# DSO_Trig.net
KiCad netlist of a schematic drawn in Altium Designer
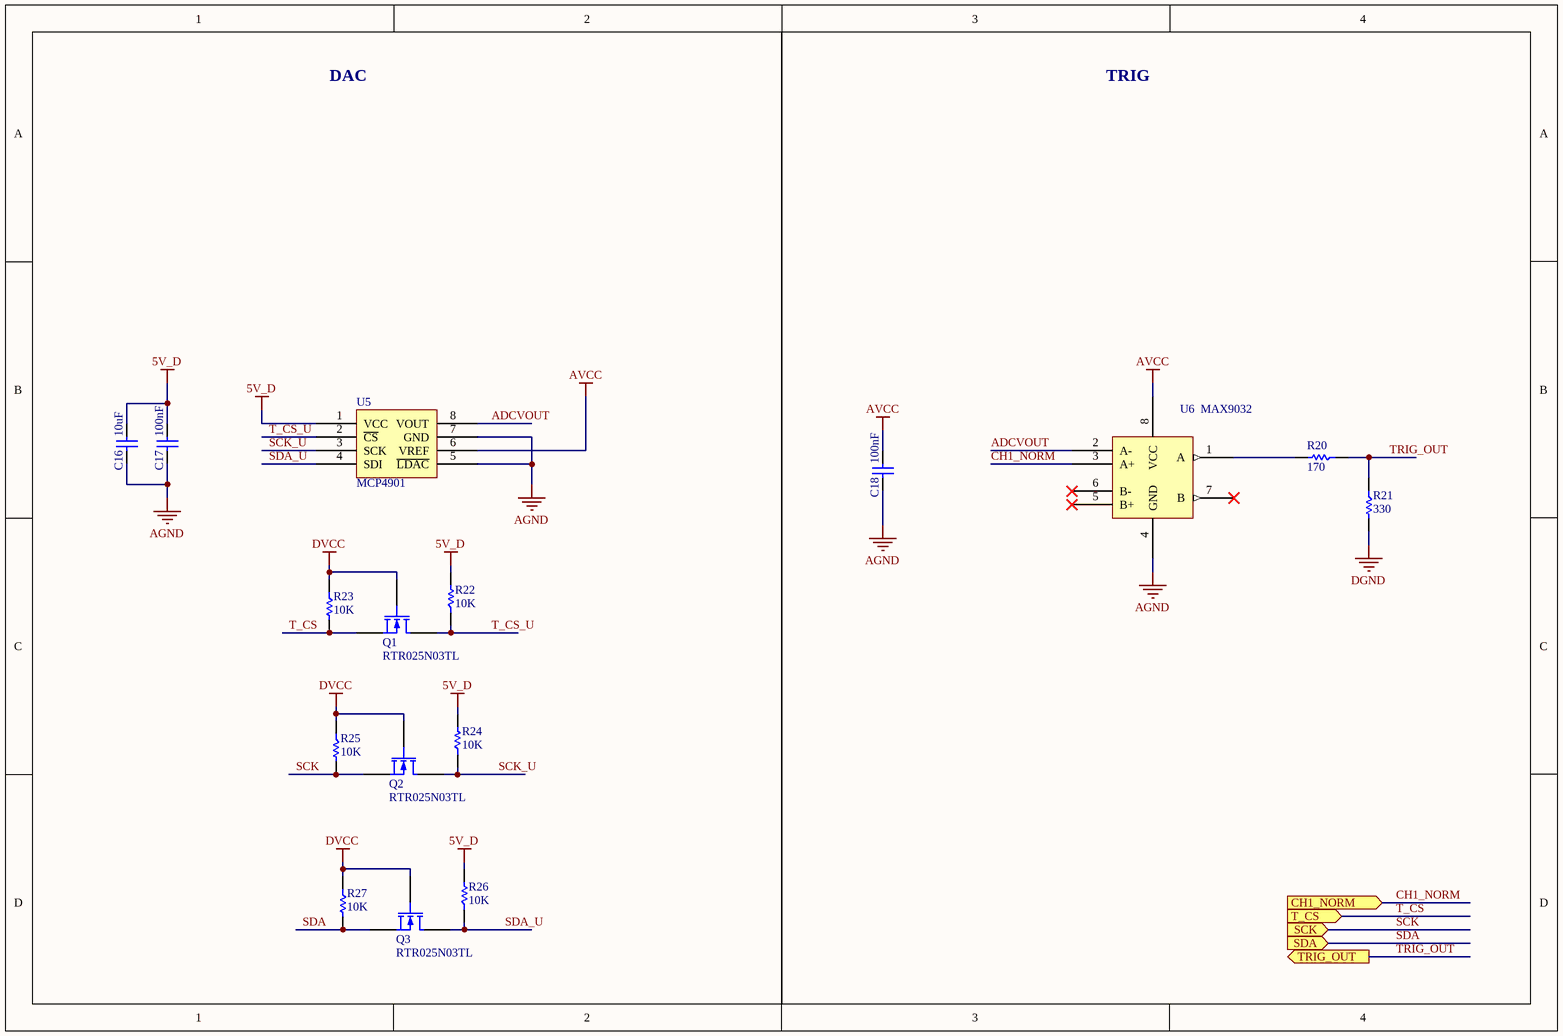
[diagram p0: DSO_Trig.SchDoc]

(export (version "E")
  (design (tool "Eeschema 10.0.6"))
  (components
    (comp (ref "C16")
      (value "10uF")
      (footprint "0805C")
      (description "Capacitor")
      (fields (field (name "REVIEWED BY") "RM - 2018/08/05"))
      (libsource (lib "DSO") (part "C"))
    )
    (comp (ref "C17")
      (value "100nF")
      (footprint "0805C")
      (description "Capacitor")
      (fields (field (name "REVIEWED BY") "RM - 2018/08/05"))
      (libsource (lib "DSO") (part "C"))
    )
    (comp (ref "C18")
      (value "100nF")
      (footprint "0805C")
      (description "Capacitor")
      (fields (field (name "REVIEWED BY") "RM - 2018/08/05"))
      (libsource (lib "DSO") (part "C"))
    )
    (comp (ref "Q1")
      (value "RTR025N03TL")
      (footprint "SOT23")
      (description "N-Channel MOSFET")
      (fields (field (name "PUBLISHER") "Altium Limited"))
      (libsource (lib "RPOT") (part "MOSFET-N"))
    )
    (comp (ref "Q2")
      (value "RTR025N03TL")
      (footprint "SOT23")
      (description "N-Channel MOSFET")
      (fields (field (name "PUBLISHER") "Altium Limited"))
      (libsource (lib "RPOT") (part "MOSFET-N"))
    )
    (comp (ref "Q3")
      (value "RTR025N03TL")
      (footprint "SOT23")
      (description "N-Channel MOSFET")
      (fields (field (name "PUBLISHER") "Altium Limited"))
      (libsource (lib "RPOT") (part "MOSFET-N"))
    )
    (comp (ref "R20")
      (value "170")
      (footprint "0805")
      (description "Resistor")
      (fields (field (name "REVIEWED BY") "RM - 2018/08/05"))
      (libsource (lib "DSO") (part "R"))
    )
    (comp (ref "R21")
      (value "330")
      (footprint "0805")
      (description "Resistor")
      (fields (field (name "REVIEWED BY") "RM - 2018/08/05"))
      (libsource (lib "DSO") (part "R"))
    )
    (comp (ref "R22")
      (value "10K")
      (footprint "0805")
      (description "Resistor")
      (fields (field (name "REVIEWED BY") "RM - 2018/08/05"))
      (libsource (lib "DSO") (part "R"))
    )
    (comp (ref "R23")
      (value "10K")
      (footprint "0805")
      (description "Resistor")
      (fields (field (name "REVIEWED BY") "RM - 2018/08/05"))
      (libsource (lib "DSO") (part "R"))
    )
    (comp (ref "R24")
      (value "10K")
      (footprint "0805")
      (description "Resistor")
      (fields (field (name "REVIEWED BY") "RM - 2018/08/05"))
      (libsource (lib "DSO") (part "R"))
    )
    (comp (ref "R25")
      (value "10K")
      (footprint "0805")
      (description "Resistor")
      (fields (field (name "REVIEWED BY") "RM - 2018/08/05"))
      (libsource (lib "DSO") (part "R"))
    )
    (comp (ref "R26")
      (value "10K")
      (footprint "0805")
      (description "Resistor")
      (fields (field (name "REVIEWED BY") "RM - 2018/08/05"))
      (libsource (lib "DSO") (part "R"))
    )
    (comp (ref "R27")
      (value "10K")
      (footprint "0805")
      (description "Resistor")
      (fields (field (name "REVIEWED BY") "RM - 2018/08/05"))
      (libsource (lib "DSO") (part "R"))
    )
    (comp (ref "U5")
      (value "MCP4901")
      (footprint "SOIC-8")
      (description "DAC 8bit SPI")
      (fields (field (name "REVIEWED BY") "RM - 2018/08/05"))
      (libsource (lib "DSO") (part "MCP4901"))
    )
    (comp (ref "U6")
      (value "MAX9032")
      (footprint "SOIC-8")
      (description "Dual Comparator")
      (fields (field (name "REVIEWED BY") "RM - 2018/08/05"))
      (libsource (lib "DSO") (part "MAX9032"))
    )
  )
  (nets
    (net (code "1") (name "/ADCVOUT") (class "Default")
      (node (ref "U5") (pin "8") (pinfunction "VOUT_8") (pintype "passive"))
      (node (ref "U6") (pin "2") (pinfunction "A-_2") (pintype "passive"))
    )
    (net (code "2") (name "/CH1_NORM") (class "Default")
      (node (ref "U6") (pin "3") (pinfunction "A+_3") (pintype "passive"))
    )
    (net (code "3") (name "/SCK") (class "Default")
      (node (ref "Q2") (pin "2") (pinfunction "2_2") (pintype "passive"))
      (node (ref "R25") (pin "2") (pintype "passive"))
    )
    (net (code "4") (name "/SCK_U") (class "Default")
      (node (ref "Q2") (pin "3") (pinfunction "3_3") (pintype "passive"))
      (node (ref "R24") (pin "1") (pintype "passive"))
      (node (ref "U5") (pin "3") (pinfunction "SCK_3") (pintype "passive"))
    )
    (net (code "5") (name "/SDA") (class "Default")
      (node (ref "Q3") (pin "2") (pinfunction "2_2") (pintype "passive"))
      (node (ref "R27") (pin "2") (pintype "passive"))
    )
    (net (code "6") (name "/SDA_U") (class "Default")
      (node (ref "Q3") (pin "3") (pinfunction "3_3") (pintype "passive"))
      (node (ref "R26") (pin "1") (pintype "passive"))
      (node (ref "U5") (pin "4") (pinfunction "SDI_4") (pintype "passive"))
    )
    (net (code "7") (name "/TRIG_OUT") (class "Default")
      (node (ref "R20") (pin "1") (pintype "passive"))
      (node (ref "R21") (pin "1") (pintype "passive"))
    )
    (net (code "8") (name "/T_CS") (class "Default")
      (node (ref "Q1") (pin "2") (pinfunction "2_2") (pintype "passive"))
      (node (ref "R23") (pin "2") (pintype "passive"))
    )
    (net (code "9") (name "/T_CS_U") (class "Default")
      (node (ref "Q1") (pin "3") (pinfunction "3_3") (pintype "passive"))
      (node (ref "R22") (pin "1") (pintype "passive"))
      (node (ref "U5") (pin "2") (pinfunction "~{CS}_2") (pintype "passive"))
    )
    (net (code "10") (name "5V_D") (class "Default")
      (node (ref "C16") (pin "1") (pinfunction "1_1") (pintype "passive"))
      (node (ref "C17") (pin "1") (pinfunction "1_1") (pintype "passive"))
      (node (ref "R22") (pin "2") (pintype "passive"))
      (node (ref "R24") (pin "2") (pintype "passive"))
      (node (ref "R26") (pin "2") (pintype "passive"))
      (node (ref "U5") (pin "1") (pinfunction "VCC_1") (pintype "passive"))
    )
    (net (code "11") (name "AGND") (class "Default")
      (node (ref "C16") (pin "2") (pinfunction "2_2") (pintype "passive"))
      (node (ref "C17") (pin "2") (pinfunction "2_2") (pintype "passive"))
      (node (ref "C18") (pin "2") (pinfunction "2_2") (pintype "passive"))
      (node (ref "U5") (pin "5") (pinfunction "~{LDAC}_5") (pintype "passive"))
      (node (ref "U5") (pin "7") (pinfunction "GND_7") (pintype "passive"))
      (node (ref "U6") (pin "4") (pinfunction "GND_4") (pintype "passive"))
    )
    (net (code "12") (name "AVCC") (class "Default")
      (node (ref "C18") (pin "1") (pinfunction "1_1") (pintype "passive"))
      (node (ref "U5") (pin "6") (pinfunction "VREF_6") (pintype "passive"))
      (node (ref "U6") (pin "8") (pinfunction "VCC_8") (pintype "passive"))
    )
    (net (code "13") (name "DGND") (class "Default") (node (ref "R21") (pin "2") (pintype "passive")))
    (net (code "14") (name "DVCC") (class "Default")
      (node (ref "Q1") (pin "1") (pinfunction "1_1") (pintype "passive"))
      (node (ref "Q2") (pin "1") (pinfunction "1_1") (pintype "passive"))
      (node (ref "Q3") (pin "1") (pinfunction "1_1") (pintype "passive"))
      (node (ref "R23") (pin "1") (pintype "passive"))
      (node (ref "R25") (pin "1") (pintype "passive"))
      (node (ref "R27") (pin "1") (pintype "passive"))
    )
    (net (code "15") (name "Net-(U6-A)") (class "Default")
      (node (ref "R20") (pin "2") (pintype "passive"))
      (node (ref "U6") (pin "1") (pinfunction "A_1") (pintype "output"))
    )
    (net (code "16") (name "unconnected-(U6-B+-Pad5)") (class "Default")
      (node (ref "U6") (pin "5") (pinfunction "B+_5") (pintype "passive+no_connect"))
    )
    (net (code "17") (name "unconnected-(U6-B--Pad6)") (class "Default")
      (node (ref "U6") (pin "6") (pinfunction "B-_6") (pintype "passive+no_connect"))
    )
    (net (code "18") (name "unconnected-(U6-B-Pad7)") (class "Default")
      (node (ref "U6") (pin "7") (pinfunction "B_7") (pintype "output+no_connect"))
    )
  )
)
